# kilo-issue3-dual.net
KiCad netlist of a schematic drawn in EAGLE
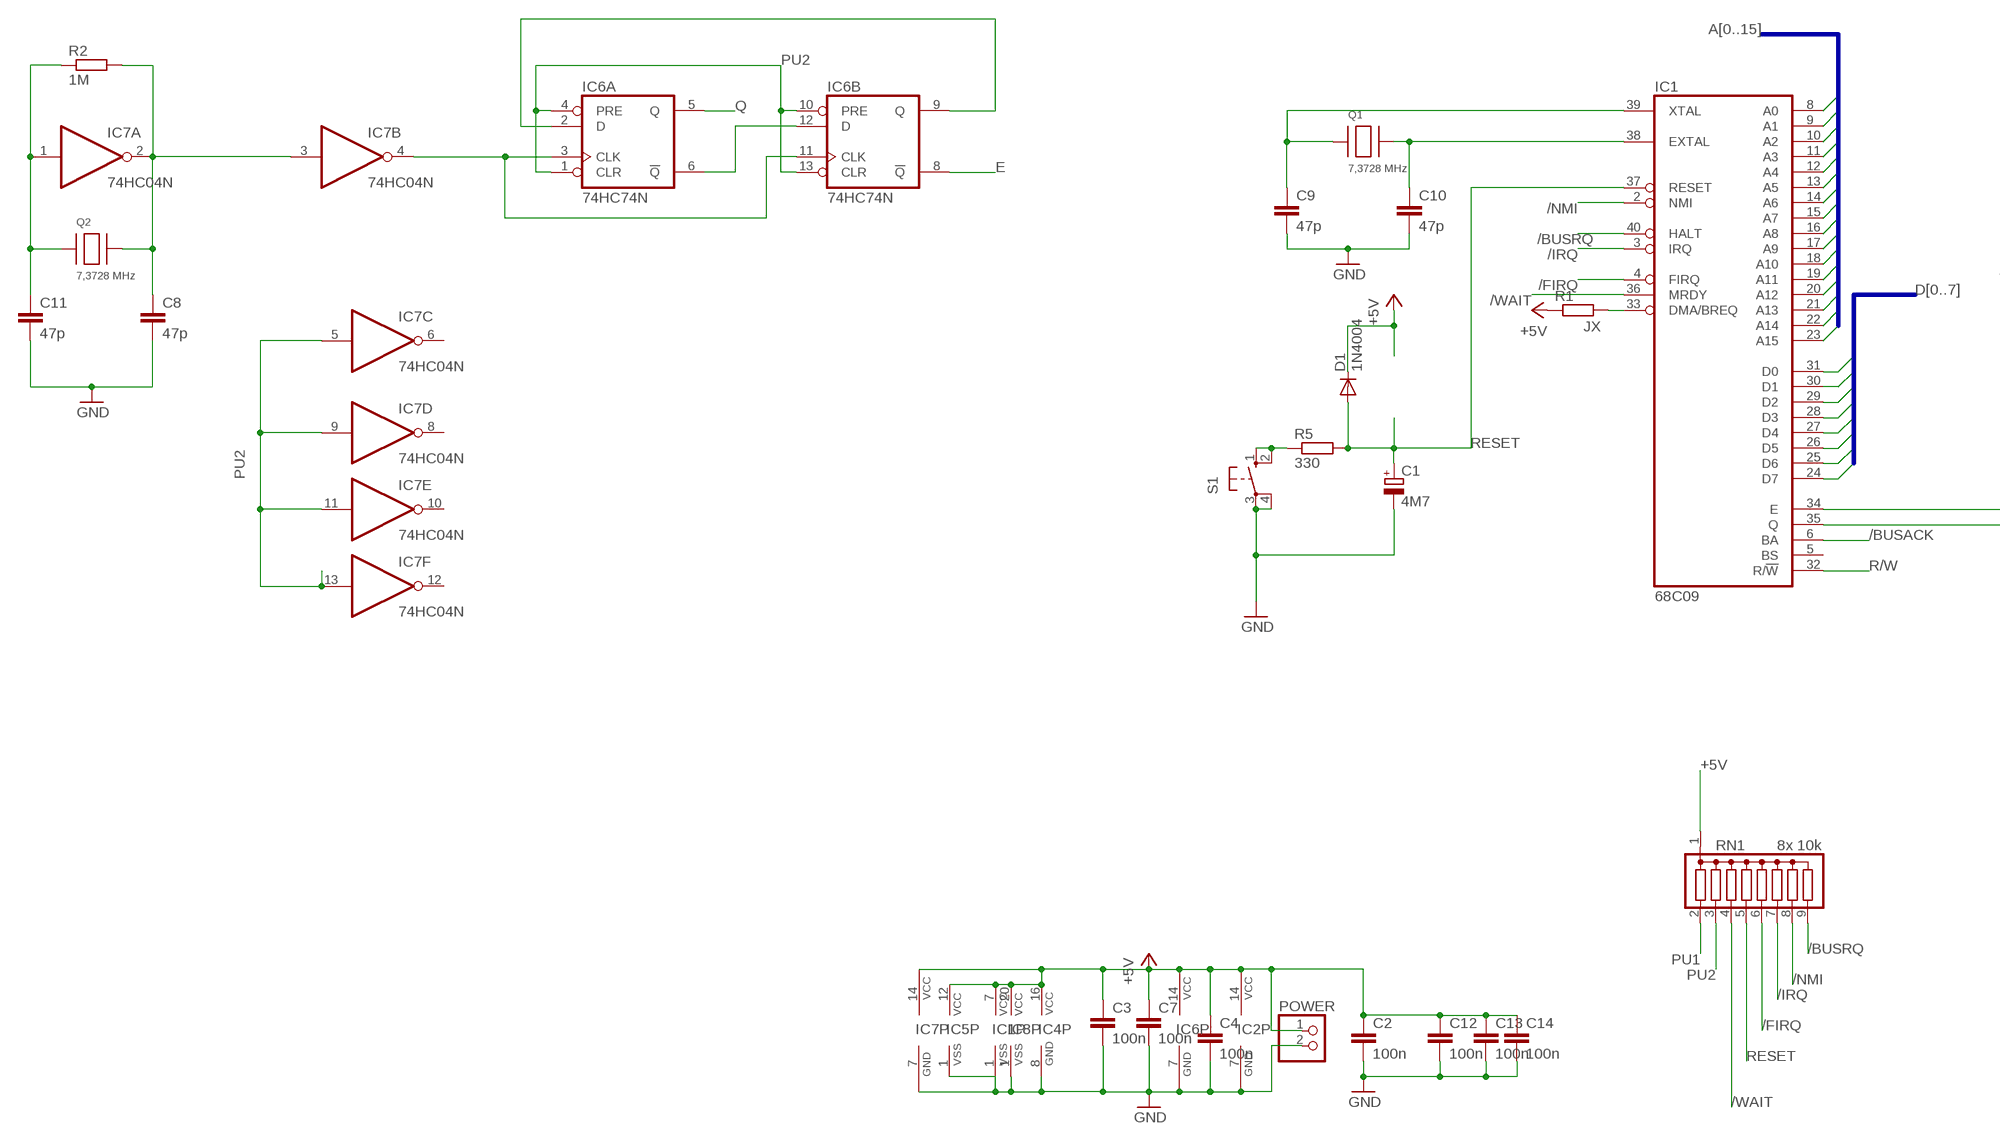
[diagram p0: schematic, sheet 1, part 1 of 2]
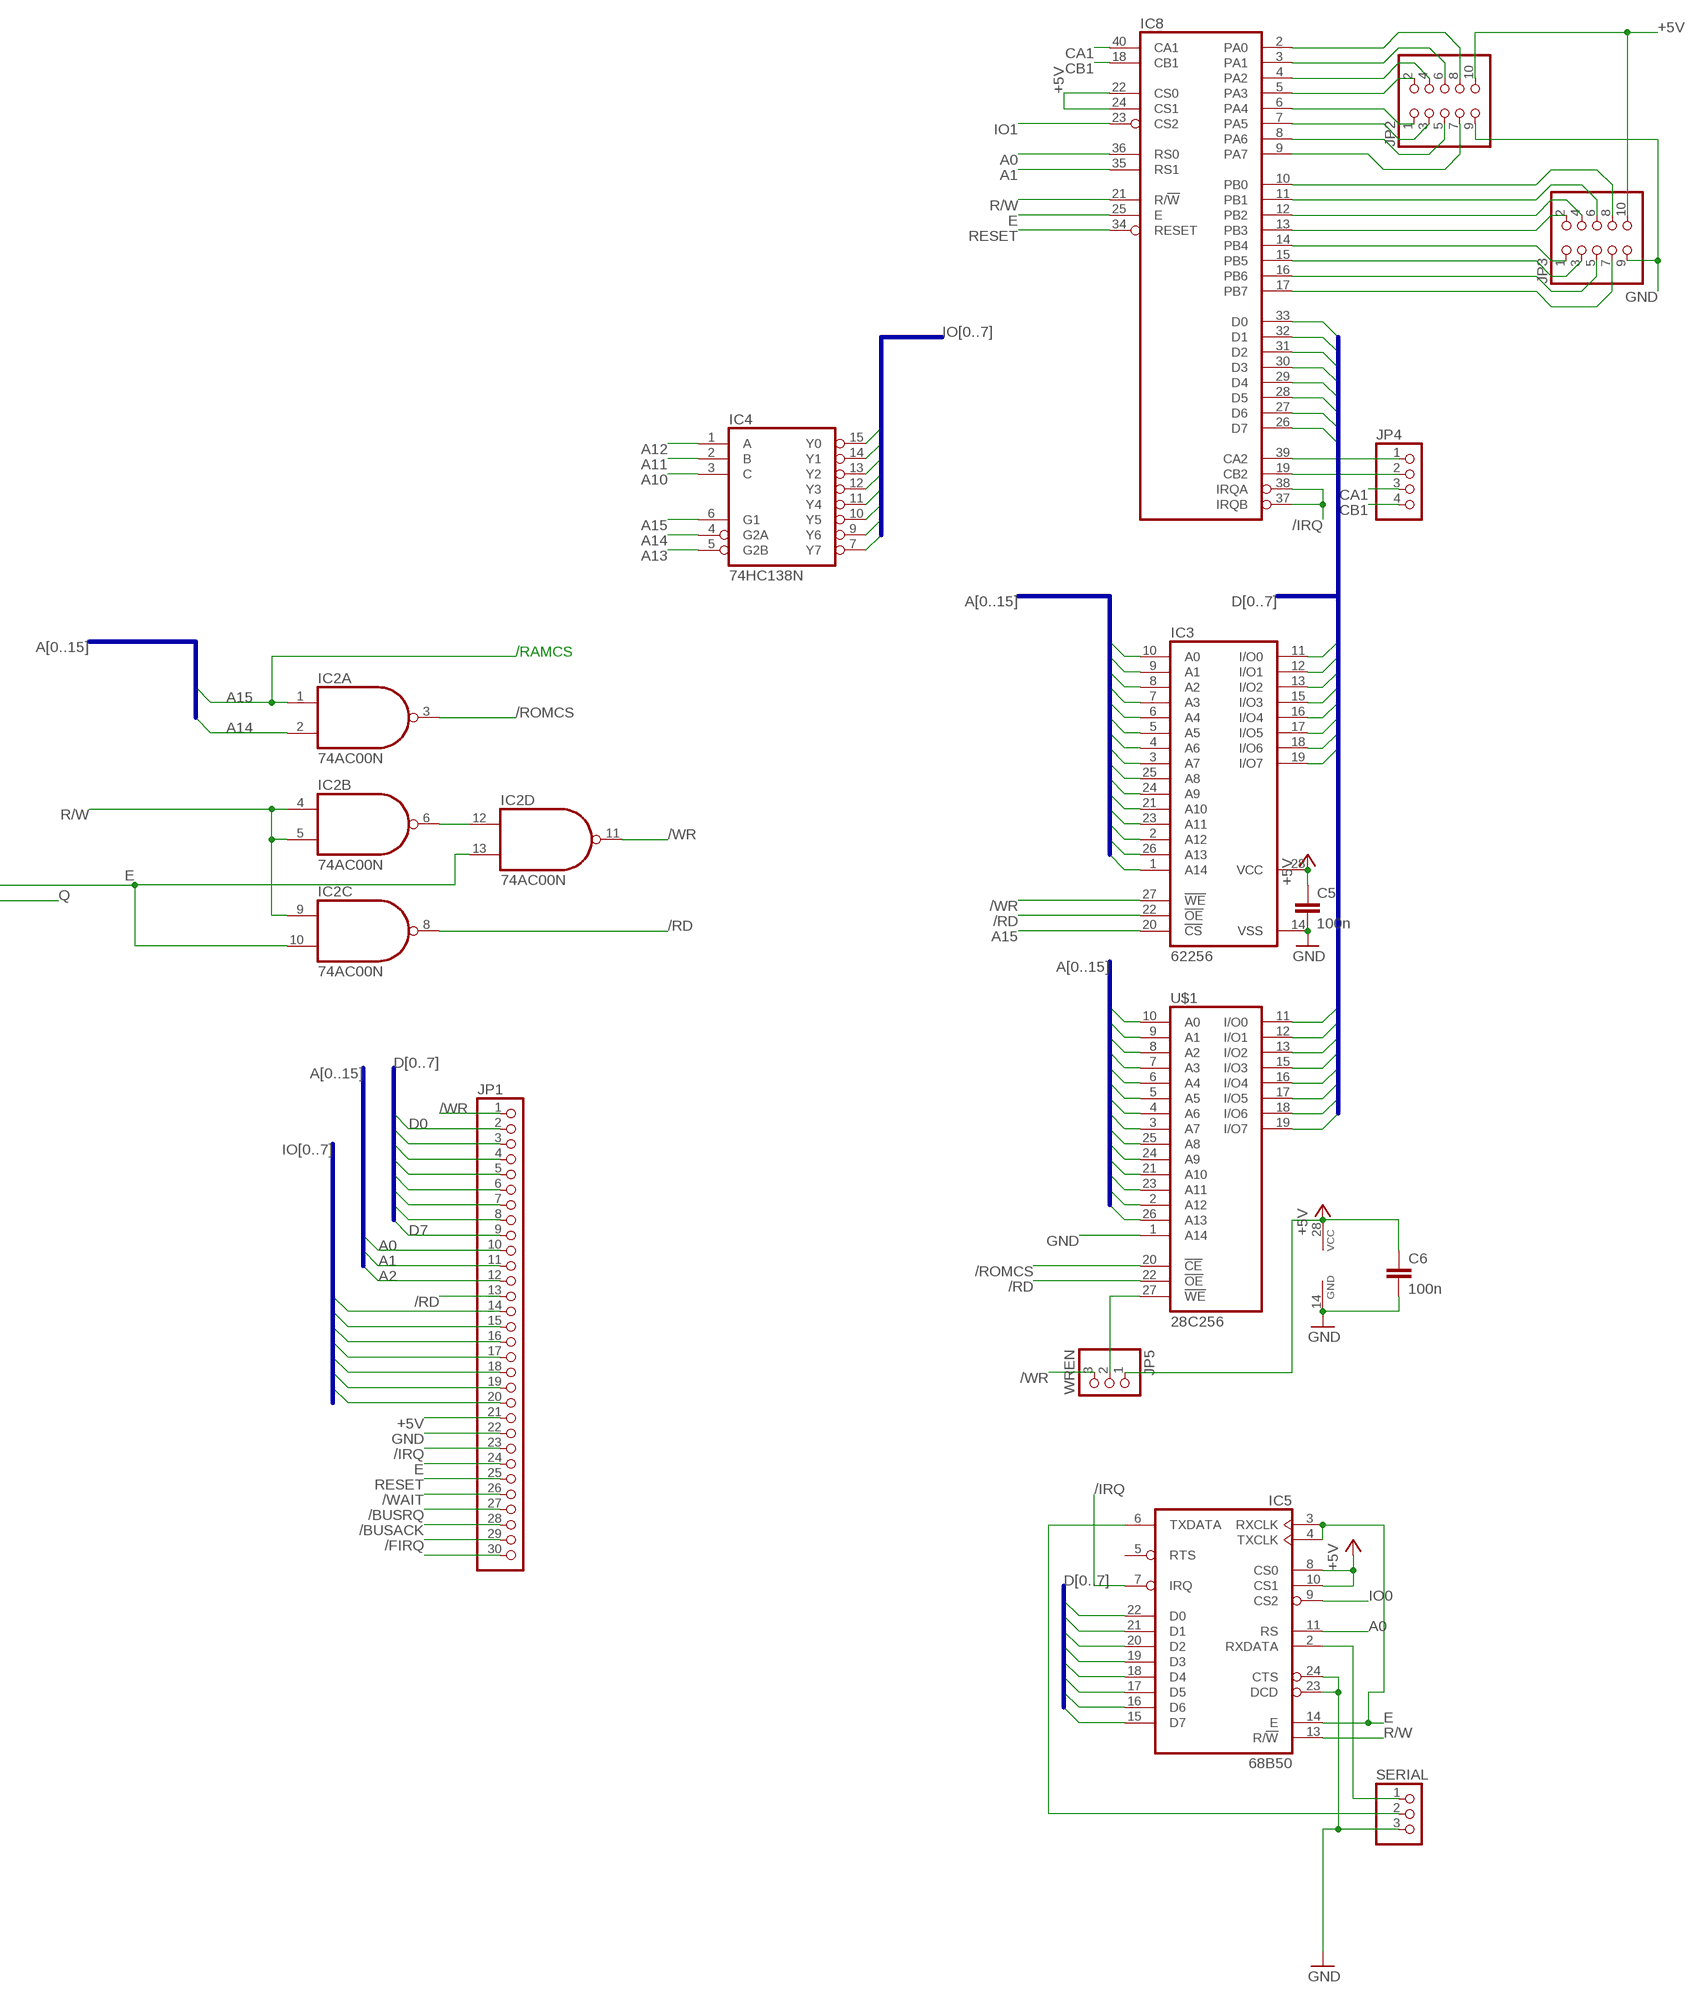
[diagram p1: schematic, sheet 1, part 2 of 2]

(export (version "E")
  (design (tool "Eeschema 10.0.6"))
  (components
    (comp (ref "C1")
      (value "4M7")
      (footprint "eagle-import:E2,5-6")
      (libsource (lib "eagle-import") (part "CPOL-EUE2.5-6"))
    )
    (comp (ref "C2")
      (value "100n")
      (footprint "eagle-import:C025-030X050")
      (libsource (lib "eagle-import") (part "C-EU025-030X050"))
    )
    (comp (ref "C3")
      (value "100n")
      (footprint "eagle-import:C025-030X050")
      (libsource (lib "eagle-import") (part "C-EU025-030X050"))
    )
    (comp (ref "C4")
      (value "100n")
      (footprint "eagle-import:C025-030X050")
      (libsource (lib "eagle-import") (part "C-EU025-030X050"))
    )
    (comp (ref "C5")
      (value "100n")
      (footprint "eagle-import:C025-030X050")
      (libsource (lib "eagle-import") (part "C-EU025-030X050"))
    )
    (comp (ref "C6")
      (value "100n")
      (footprint "eagle-import:C025-030X050")
      (libsource (lib "eagle-import") (part "C-EU025-030X050"))
    )
    (comp (ref "C7")
      (value "100n")
      (footprint "eagle-import:C025-030X050")
      (libsource (lib "eagle-import") (part "C-EU025-030X050"))
    )
    (comp (ref "C8")
      (value "47p")
      (footprint "eagle-import:C025-030X050")
      (libsource (lib "eagle-import") (part "C-EU025-030X050"))
    )
    (comp (ref "C9")
      (value "47p")
      (footprint "eagle-import:C025-030X050")
      (libsource (lib "eagle-import") (part "C-EU025-030X050"))
    )
    (comp (ref "C10")
      (value "47p")
      (footprint "eagle-import:C025-030X050")
      (libsource (lib "eagle-import") (part "C-EU025-030X050"))
    )
    (comp (ref "C11")
      (value "47p")
      (footprint "eagle-import:C025-030X050")
      (libsource (lib "eagle-import") (part "C-EU025-030X050"))
    )
    (comp (ref "C12")
      (value "100n")
      (footprint "eagle-import:C025-030X050")
      (libsource (lib "eagle-import") (part "C-EU025-030X050"))
    )
    (comp (ref "C13")
      (value "100n")
      (footprint "eagle-import:C025-030X050")
      (libsource (lib "eagle-import") (part "C-EU025-030X050"))
    )
    (comp (ref "C14")
      (value "100n")
      (footprint "eagle-import:C025-030X050")
      (libsource (lib "eagle-import") (part "C-EU025-030X050"))
    )
    (comp (ref "D1")
      (value "1N4004")
      (footprint "eagle-import:DO41-10")
      (libsource (lib "eagle-import") (part "1N4004"))
    )
    (comp (ref "IC1")
      (value "68C09")
      (footprint "eagle-import:DIL40")
      (fields (field (name "MF") "NTE ELECTRONICS") (field (name "MPN") "NTE6809"))
      (libsource (lib "eagle-import") (part "6809"))
    )
    (comp (ref "IC2")
      (value "74AC00N")
      (footprint "eagle-import:DIL14")
      (libsource (lib "eagle-import") (part "7400NALS"))
    )
    (comp (ref "IC3")
      (value "62256")
      (footprint "eagle-import:DIL28-6")
      (libsource (lib "eagle-import") (part "62256P"))
    )
    (comp (ref "IC4")
      (value "74HC138N")
      (footprint "eagle-import:DIL16")
      (libsource (lib "eagle-import") (part "74138NHC"))
    )
    (comp (ref "IC5")
      (value "68B50")
      (footprint "eagle-import:DIL24")
      (fields (field (name "MF") "NTE ELECTRONICS") (field (name "MPN") "NTE6850"))
      (libsource (lib "eagle-import") (part "6850"))
    )
    (comp (ref "IC6")
      (value "74HC74N")
      (footprint "eagle-import:DIL14")
      (libsource (lib "eagle-import") (part "7474NLS"))
    )
    (comp (ref "IC7")
      (value "74HC04N")
      (footprint "eagle-import:DIL14")
      (libsource (lib "eagle-import") (part "7404NALS"))
    )
    (comp (ref "IC8")
      (value "6821")
      (footprint "eagle-import:DIL40")
      (fields (field (name "MF") "NTE ELECTRONICS") (field (name "MPN") "NTE6821"))
      (libsource (lib "eagle-import") (part "6821"))
    )
    (comp (ref "JP1")
      (value "PINHD-1X30")
      (footprint "eagle-import:1X30")
      (libsource (lib "eagle-import") (part "PINHD-1X30"))
    )
    (comp (ref "JP2")
      (value "PINHD-2X5")
      (footprint "eagle-import:2X05")
      (libsource (lib "eagle-import") (part "PINHD-2X5"))
    )
    (comp (ref "JP3")
      (value "PINHD-2X5")
      (footprint "eagle-import:2X05")
      (libsource (lib "eagle-import") (part "PINHD-2X5"))
    )
    (comp (ref "JP4")
      (value "PINHD-1X4")
      (footprint "eagle-import:1X04")
      (libsource (lib "eagle-import") (part "PINHD-1X4"))
    )
    (comp (ref "JP5")
      (value "WREN")
      (footprint "eagle-import:1X03")
      (libsource (lib "eagle-import") (part "pinhead_325_PINHD-1X3"))
    )
    (comp (ref "POWER")
      (value "PINHD-1X2")
      (footprint "eagle-import:1X02")
      (libsource (lib "eagle-import") (part "PINHD-1X2"))
    )
    (comp (ref "Q1")
      (value "7,3728 MHz")
      (footprint "eagle-import:HC49US")
      (libsource (lib "eagle-import") (part "306010080_XTAL_8MHZ_HC49US"))
    )
    (comp (ref "Q2")
      (value "7,3728 MHz")
      (footprint "eagle-import:HC49US")
      (libsource (lib "eagle-import") (part "306010080_XTAL_8MHZ_HC49US"))
    )
    (comp (ref "R1")
      (value "JX")
      (footprint "eagle-import:M0805")
      (libsource (lib "eagle-import") (part "rcl_334_R-EU_M0805"))
    )
    (comp (ref "R2")
      (value "1M")
      (footprint "eagle-import:0207_7")
      (libsource (lib "eagle-import") (part "R-EU_0207/7"))
    )
    (comp (ref "R5")
      (value "330")
      (footprint "eagle-import:0207_7")
      (libsource (lib "eagle-import") (part "R-EU_0207/7"))
    )
    (comp (ref "RN1")
      (value "8x 10k")
      (footprint "eagle-import:SIL9")
      (libsource (lib "eagle-import") (part "G08R"))
    )
    (comp (ref "S1")
      (value "40-XX")
      (footprint "eagle-import:B3F-40XX")
      (fields (field (name "MF") "OMRON COMPONENTS USA") (field (name "MPN") "B3F-4000"))
      (libsource (lib "eagle-import") (part "40-XX"))
    )
    (comp (ref "SERIAL")
      (value "PINHD-1X3")
      (footprint "eagle-import:1X03")
      (libsource (lib "eagle-import") (part "PINHD-1X3"))
    )
    (comp (ref "U$1")
      (value "28C256")
      (footprint "eagle-import:DIL28")
      (libsource (lib "eagle-import") (part "28C256"))
    )
  )
  (nets
    (net (code "1") (name "+5V") (class "Default")
      (node (ref "C12") (pin "1") (pinfunction "1_1") (pintype "passive"))
      (node (ref "C13") (pin "1") (pinfunction "1_1") (pintype "passive"))
      (node (ref "C14") (pin "1") (pinfunction "1_1") (pintype "passive"))
      (node (ref "C2") (pin "1") (pinfunction "1_1") (pintype "passive"))
      (node (ref "C3") (pin "1") (pinfunction "1_1") (pintype "passive"))
      (node (ref "C4") (pin "1") (pinfunction "1_1") (pintype "passive"))
      (node (ref "C5") (pin "1") (pinfunction "1_1") (pintype "passive"))
      (node (ref "C6") (pin "1") (pinfunction "1_1") (pintype "passive"))
      (node (ref "C7") (pin "1") (pinfunction "1_1") (pintype "passive"))
      (node (ref "D1") (pin "C") (pinfunction "C_C") (pintype "passive"))
      (node (ref "IC1") (pin "7") (pinfunction "VCC_7") (pintype "power_in"))
      (node (ref "IC2") (pin "14") (pinfunction "VCC_14") (pintype "power_in"))
      (node (ref "IC3") (pin "28") (pinfunction "VCC_28") (pintype "power_in"))
      (node (ref "IC4") (pin "16") (pinfunction "VCC_16") (pintype "power_in"))
      (node (ref "IC5") (pin "10") (pinfunction "CS1_10") (pintype "input"))
      (node (ref "IC5") (pin "12") (pinfunction "VCC_12") (pintype "power_in"))
      (node (ref "IC5") (pin "8") (pinfunction "CS0_8") (pintype "input"))
      (node (ref "IC6") (pin "14") (pinfunction "VCC_14") (pintype "power_in"))
      (node (ref "IC7") (pin "14") (pinfunction "VCC_14") (pintype "power_in"))
      (node (ref "IC8") (pin "20") (pinfunction "VCC_20") (pintype "power_in"))
      (node (ref "IC8") (pin "22") (pinfunction "CS0_22") (pintype "input"))
      (node (ref "IC8") (pin "24") (pinfunction "CS1_24") (pintype "input"))
      (node (ref "JP1") (pin "21") (pinfunction "21_21") (pintype "passive"))
      (node (ref "JP2") (pin "10") (pinfunction "10_10") (pintype "passive"))
      (node (ref "JP3") (pin "10") (pinfunction "10_10") (pintype "passive"))
      (node (ref "JP5") (pin "1") (pinfunction "1_1") (pintype "passive"))
      (node (ref "POWER") (pin "1") (pinfunction "1_1") (pintype "passive"))
      (node (ref "R1") (pin "1") (pinfunction "1_1") (pintype "passive"))
      (node (ref "RN1") (pin "1") (pinfunction "1_1") (pintype "passive"))
      (node (ref "U$1") (pin "28") (pinfunction "VCC_28") (pintype "power_in"))
    )
    (net (code "5") (name "A0") (class "Default")
      (node (ref "IC1") (pin "8") (pinfunction "A0_8") (pintype "tri_state"))
      (node (ref "IC3") (pin "10") (pinfunction "A0_10") (pintype "input"))
      (node (ref "IC5") (pin "11") (pinfunction "RS_11") (pintype "input"))
      (node (ref "IC8") (pin "36") (pinfunction "RS0_36") (pintype "input"))
      (node (ref "JP1") (pin "10") (pinfunction "10_10") (pintype "passive"))
      (node (ref "U$1") (pin "10") (pinfunction "A0_10") (pintype "input"))
    )
    (net (code "6") (name "A1") (class "Default")
      (node (ref "IC1") (pin "9") (pinfunction "A1_9") (pintype "tri_state"))
      (node (ref "IC3") (pin "9") (pinfunction "A1_9") (pintype "input"))
      (node (ref "IC8") (pin "35") (pinfunction "RS1_35") (pintype "input"))
      (node (ref "JP1") (pin "11") (pinfunction "11_11") (pintype "passive"))
      (node (ref "U$1") (pin "9") (pinfunction "A1_9") (pintype "input"))
    )
    (net (code "7") (name "A2") (class "Default")
      (node (ref "IC1") (pin "10") (pinfunction "A2_10") (pintype "tri_state"))
      (node (ref "IC3") (pin "8") (pinfunction "A2_8") (pintype "input"))
      (node (ref "JP1") (pin "12") (pinfunction "12_12") (pintype "passive"))
      (node (ref "U$1") (pin "8") (pinfunction "A2_8") (pintype "input"))
    )
    (net (code "8") (name "A3") (class "Default")
      (node (ref "IC1") (pin "11") (pinfunction "A3_11") (pintype "tri_state"))
      (node (ref "IC3") (pin "7") (pinfunction "A3_7") (pintype "input"))
      (node (ref "U$1") (pin "7") (pinfunction "A3_7") (pintype "input"))
    )
    (net (code "9") (name "A4") (class "Default")
      (node (ref "IC1") (pin "12") (pinfunction "A4_12") (pintype "tri_state"))
      (node (ref "IC3") (pin "6") (pinfunction "A4_6") (pintype "input"))
      (node (ref "U$1") (pin "6") (pinfunction "A4_6") (pintype "input"))
    )
    (net (code "10") (name "A5") (class "Default")
      (node (ref "IC1") (pin "13") (pinfunction "A5_13") (pintype "tri_state"))
      (node (ref "IC3") (pin "5") (pinfunction "A5_5") (pintype "input"))
      (node (ref "U$1") (pin "5") (pinfunction "A5_5") (pintype "input"))
    )
    (net (code "11") (name "A6") (class "Default")
      (node (ref "IC1") (pin "14") (pinfunction "A6_14") (pintype "tri_state"))
      (node (ref "IC3") (pin "4") (pinfunction "A6_4") (pintype "input"))
      (node (ref "U$1") (pin "4") (pinfunction "A6_4") (pintype "input"))
    )
    (net (code "12") (name "A7") (class "Default")
      (node (ref "IC1") (pin "15") (pinfunction "A7_15") (pintype "tri_state"))
      (node (ref "IC3") (pin "3") (pinfunction "A7_3") (pintype "input"))
      (node (ref "U$1") (pin "3") (pinfunction "A7_3") (pintype "input"))
    )
    (net (code "13") (name "A8") (class "Default")
      (node (ref "IC1") (pin "16") (pinfunction "A8_16") (pintype "tri_state"))
      (node (ref "IC3") (pin "25") (pinfunction "A8_25") (pintype "input"))
      (node (ref "U$1") (pin "25") (pinfunction "A8_25") (pintype "input"))
    )
    (net (code "14") (name "A9") (class "Default")
      (node (ref "IC1") (pin "17") (pinfunction "A9_17") (pintype "tri_state"))
      (node (ref "IC3") (pin "24") (pinfunction "A9_24") (pintype "input"))
      (node (ref "U$1") (pin "24") (pinfunction "A9_24") (pintype "input"))
    )
    (net (code "15") (name "A10") (class "Default")
      (node (ref "IC1") (pin "18") (pinfunction "A10_18") (pintype "tri_state"))
      (node (ref "IC3") (pin "21") (pinfunction "A10_21") (pintype "input"))
      (node (ref "IC4") (pin "3") (pinfunction "C_3") (pintype "input"))
      (node (ref "U$1") (pin "21") (pinfunction "A10_21") (pintype "input"))
    )
    (net (code "16") (name "A11") (class "Default")
      (node (ref "IC1") (pin "19") (pinfunction "A11_19") (pintype "tri_state"))
      (node (ref "IC3") (pin "23") (pinfunction "A11_23") (pintype "input"))
      (node (ref "IC4") (pin "2") (pinfunction "B_2") (pintype "input"))
      (node (ref "U$1") (pin "23") (pinfunction "A11_23") (pintype "input"))
    )
    (net (code "17") (name "A12") (class "Default")
      (node (ref "IC1") (pin "20") (pinfunction "A12_20") (pintype "tri_state"))
      (node (ref "IC3") (pin "2") (pinfunction "A12_2") (pintype "input"))
      (node (ref "IC4") (pin "1") (pinfunction "A_1") (pintype "input"))
      (node (ref "U$1") (pin "2") (pinfunction "A12_2") (pintype "input"))
    )
    (net (code "18") (name "A13") (class "Default")
      (node (ref "IC1") (pin "21") (pinfunction "A13_21") (pintype "tri_state"))
      (node (ref "IC3") (pin "26") (pinfunction "A13_26") (pintype "input"))
      (node (ref "IC4") (pin "5") (pinfunction "G2B_5") (pintype "input"))
      (node (ref "U$1") (pin "26") (pinfunction "A13_26") (pintype "input"))
    )
    (net (code "19") (name "A14") (class "Default")
      (node (ref "IC1") (pin "22") (pinfunction "A14_22") (pintype "tri_state"))
      (node (ref "IC2") (pin "2") (pinfunction "I1_2") (pintype "input"))
      (node (ref "IC3") (pin "1") (pinfunction "A14_1") (pintype "input"))
      (node (ref "IC4") (pin "4") (pinfunction "G2A_4") (pintype "input"))
    )
    (net (code "20") (name "A15") (class "Default")
      (node (ref "IC1") (pin "23") (pinfunction "A15_23") (pintype "tri_state"))
      (node (ref "IC2") (pin "1") (pinfunction "I0_1") (pintype "input"))
      (node (ref "IC3") (pin "20") (pinfunction "~{CS}_20") (pintype "input"))
      (node (ref "IC4") (pin "6") (pinfunction "G1_6") (pintype "input"))
    )
    (net (code "21") (name "CA1") (class "Default")
      (node (ref "IC8") (pin "40") (pinfunction "CA1_40") (pintype "input"))
      (node (ref "JP4") (pin "3") (pinfunction "3_3") (pintype "passive"))
    )
    (net (code "22") (name "CB1") (class "Default")
      (node (ref "IC8") (pin "18") (pinfunction "CB1_18") (pintype "input"))
      (node (ref "JP4") (pin "4") (pinfunction "4_4") (pintype "passive"))
    )
    (net (code "23") (name "D0") (class "Default")
      (node (ref "IC1") (pin "31") (pinfunction "D0_31") (pintype "bidirectional"))
      (node (ref "IC3") (pin "11") (pinfunction "I/O0_11") (pintype "bidirectional"))
      (node (ref "IC5") (pin "22") (pinfunction "D0_22") (pintype "bidirectional"))
      (node (ref "IC8") (pin "33") (pinfunction "D0_33") (pintype "bidirectional"))
      (node (ref "JP1") (pin "2") (pinfunction "2_2") (pintype "passive"))
      (node (ref "U$1") (pin "11") (pinfunction "I/O0_11") (pintype "tri_state"))
    )
    (net (code "24") (name "D1") (class "Default")
      (node (ref "IC1") (pin "30") (pinfunction "D1_30") (pintype "bidirectional"))
      (node (ref "IC3") (pin "12") (pinfunction "I/O1_12") (pintype "bidirectional"))
      (node (ref "IC5") (pin "21") (pinfunction "D1_21") (pintype "bidirectional"))
      (node (ref "IC8") (pin "32") (pinfunction "D1_32") (pintype "bidirectional"))
      (node (ref "JP1") (pin "3") (pinfunction "3_3") (pintype "passive"))
      (node (ref "U$1") (pin "12") (pinfunction "I/O1_12") (pintype "tri_state"))
    )
    (net (code "25") (name "D2") (class "Default")
      (node (ref "IC1") (pin "29") (pinfunction "D2_29") (pintype "bidirectional"))
      (node (ref "IC3") (pin "13") (pinfunction "I/O2_13") (pintype "bidirectional"))
      (node (ref "IC5") (pin "20") (pinfunction "D2_20") (pintype "bidirectional"))
      (node (ref "IC8") (pin "31") (pinfunction "D2_31") (pintype "bidirectional"))
      (node (ref "JP1") (pin "4") (pinfunction "4_4") (pintype "passive"))
      (node (ref "U$1") (pin "13") (pinfunction "I/O2_13") (pintype "tri_state"))
    )
    (net (code "26") (name "D3") (class "Default")
      (node (ref "IC1") (pin "28") (pinfunction "D3_28") (pintype "bidirectional"))
      (node (ref "IC3") (pin "15") (pinfunction "I/O3_15") (pintype "bidirectional"))
      (node (ref "IC5") (pin "19") (pinfunction "D3_19") (pintype "bidirectional"))
      (node (ref "IC8") (pin "30") (pinfunction "D3_30") (pintype "bidirectional"))
      (node (ref "JP1") (pin "5") (pinfunction "5_5") (pintype "passive"))
      (node (ref "U$1") (pin "15") (pinfunction "I/O3_15") (pintype "tri_state"))
    )
    (net (code "27") (name "D4") (class "Default")
      (node (ref "IC1") (pin "27") (pinfunction "D4_27") (pintype "bidirectional"))
      (node (ref "IC3") (pin "16") (pinfunction "I/O4_16") (pintype "bidirectional"))
      (node (ref "IC5") (pin "18") (pinfunction "D4_18") (pintype "bidirectional"))
      (node (ref "IC8") (pin "29") (pinfunction "D4_29") (pintype "bidirectional"))
      (node (ref "JP1") (pin "6") (pinfunction "6_6") (pintype "passive"))
      (node (ref "U$1") (pin "16") (pinfunction "I/O4_16") (pintype "tri_state"))
    )
    (net (code "28") (name "D5") (class "Default")
      (node (ref "IC1") (pin "26") (pinfunction "D5_26") (pintype "bidirectional"))
      (node (ref "IC3") (pin "17") (pinfunction "I/O5_17") (pintype "bidirectional"))
      (node (ref "IC5") (pin "17") (pinfunction "D5_17") (pintype "bidirectional"))
      (node (ref "IC8") (pin "28") (pinfunction "D5_28") (pintype "bidirectional"))
      (node (ref "JP1") (pin "7") (pinfunction "7_7") (pintype "passive"))
      (node (ref "U$1") (pin "17") (pinfunction "I/O5_17") (pintype "tri_state"))
    )
    (net (code "29") (name "D6") (class "Default")
      (node (ref "IC1") (pin "25") (pinfunction "D6_25") (pintype "bidirectional"))
      (node (ref "IC3") (pin "18") (pinfunction "I/O6_18") (pintype "bidirectional"))
      (node (ref "IC5") (pin "16") (pinfunction "D6_16") (pintype "bidirectional"))
      (node (ref "IC8") (pin "27") (pinfunction "D6_27") (pintype "bidirectional"))
      (node (ref "JP1") (pin "8") (pinfunction "8_8") (pintype "passive"))
      (node (ref "U$1") (pin "18") (pinfunction "I/O6_18") (pintype "tri_state"))
    )
    (net (code "30") (name "D7") (class "Default")
      (node (ref "IC1") (pin "24") (pinfunction "D7_24") (pintype "bidirectional"))
      (node (ref "IC3") (pin "19") (pinfunction "I/O7_19") (pintype "bidirectional"))
      (node (ref "IC5") (pin "15") (pinfunction "D7_15") (pintype "bidirectional"))
      (node (ref "IC8") (pin "26") (pinfunction "D7_26") (pintype "bidirectional"))
      (node (ref "JP1") (pin "9") (pinfunction "9_9") (pintype "passive"))
      (node (ref "U$1") (pin "19") (pinfunction "I/O7_19") (pintype "tri_state"))
    )
    (net (code "31") (name "E") (class "Default")
      (node (ref "IC1") (pin "34") (pinfunction "E_34") (pintype "output"))
      (node (ref "IC2") (pin "10") (pinfunction "I1_10") (pintype "input"))
      (node (ref "IC2") (pin "13") (pinfunction "I1_13") (pintype "input"))
      (node (ref "IC5") (pin "14") (pinfunction "E_14") (pintype "input"))
      (node (ref "IC5") (pin "3") (pinfunction "RXCLK_3") (pintype "input"))
      (node (ref "IC5") (pin "4") (pinfunction "TXCLK_4") (pintype "input"))
      (node (ref "IC6") (pin "8") (pinfunction "~{Q}_8") (pintype "output"))
      (node (ref "IC8") (pin "25") (pinfunction "E_25") (pintype "input"))
      (node (ref "JP1") (pin "24") (pinfunction "24_24") (pintype "passive"))
    )
    (net (code "32") (name "GND") (class "Default")
      (node (ref "C1") (pin "-") (pinfunction "-_-") (pintype "passive"))
      (node (ref "C10") (pin "2") (pinfunction "2_2") (pintype "passive"))
      (node (ref "C11") (pin "2") (pinfunction "2_2") (pintype "passive"))
      (node (ref "C12") (pin "2") (pinfunction "2_2") (pintype "passive"))
      (node (ref "C13") (pin "2") (pinfunction "2_2") (pintype "passive"))
      (node (ref "C14") (pin "2") (pinfunction "2_2") (pintype "passive"))
      (node (ref "C2") (pin "2") (pinfunction "2_2") (pintype "passive"))
      (node (ref "C3") (pin "2") (pinfunction "2_2") (pintype "passive"))
      (node (ref "C4") (pin "2") (pinfunction "2_2") (pintype "passive"))
      (node (ref "C5") (pin "2") (pinfunction "2_2") (pintype "passive"))
      (node (ref "C6") (pin "2") (pinfunction "2_2") (pintype "passive"))
      (node (ref "C7") (pin "2") (pinfunction "2_2") (pintype "passive"))
      (node (ref "C8") (pin "2") (pinfunction "2_2") (pintype "passive"))
      (node (ref "C9") (pin "2") (pinfunction "2_2") (pintype "passive"))
      (node (ref "IC1") (pin "1") (pinfunction "VSS_1") (pintype "power_in"))
      (node (ref "IC2") (pin "7") (pinfunction "GND_7") (pintype "power_in"))
      (node (ref "IC3") (pin "14") (pinfunction "VSS_14") (pintype "power_in"))
      (node (ref "IC4") (pin "8") (pinfunction "GND_8") (pintype "power_in"))
      (node (ref "IC5") (pin "1") (pinfunction "VSS_1") (pintype "power_in"))
      (node (ref "IC5") (pin "23") (pinfunction "DCD_23") (pintype "input"))
      (node (ref "IC5") (pin "24") (pinfunction "CTS_24") (pintype "input"))
      (node (ref "IC6") (pin "7") (pinfunction "GND_7") (pintype "power_in"))
      (node (ref "IC7") (pin "7") (pinfunction "GND_7") (pintype "power_in"))
      (node (ref "IC8") (pin "1") (pinfunction "VSS_1") (pintype "power_in"))
      (node (ref "JP1") (pin "22") (pinfunction "22_22") (pintype "passive"))
      (node (ref "JP2") (pin "9") (pinfunction "9_9") (pintype "passive"))
      (node (ref "JP3") (pin "9") (pinfunction "9_9") (pintype "passive"))
      (node (ref "POWER") (pin "2") (pinfunction "2_2") (pintype "passive"))
      (node (ref "S1") (pin "3") (pinfunction "P_3") (pintype "passive"))
      (node (ref "S1") (pin "4") (pinfunction "P1_4") (pintype "passive"))
      (node (ref "SERIAL") (pin "3") (pinfunction "3_3") (pintype "passive"))
      (node (ref "U$1") (pin "1") (pinfunction "A14_1") (pintype "input"))
      (node (ref "U$1") (pin "14") (pinfunction "GND_14") (pintype "power_in"))
    )
    (net (code "33") (name "IO0") (class "Default")
      (node (ref "IC4") (pin "15") (pinfunction "Y0_15") (pintype "output"))
      (node (ref "IC5") (pin "9") (pinfunction "CS2_9") (pintype "input"))
    )
    (net (code "34") (name "IO1") (class "Default")
      (node (ref "IC4") (pin "14") (pinfunction "Y1_14") (pintype "output"))
      (node (ref "IC8") (pin "23") (pinfunction "CS2_23") (pintype "input"))
      (node (ref "JP1") (pin "14") (pinfunction "14_14") (pintype "passive"))
    )
    (net (code "35") (name "IO2") (class "Default")
      (node (ref "IC4") (pin "13") (pinfunction "Y2_13") (pintype "output"))
      (node (ref "JP1") (pin "15") (pinfunction "15_15") (pintype "passive"))
    )
    (net (code "36") (name "IO3") (class "Default")
      (node (ref "IC4") (pin "12") (pinfunction "Y3_12") (pintype "output"))
      (node (ref "JP1") (pin "16") (pinfunction "16_16") (pintype "passive"))
    )
    (net (code "37") (name "IO4") (class "Default")
      (node (ref "IC4") (pin "11") (pinfunction "Y4_11") (pintype "output"))
      (node (ref "JP1") (pin "17") (pinfunction "17_17") (pintype "passive"))
    )
    (net (code "38") (name "IO5") (class "Default")
      (node (ref "IC4") (pin "10") (pinfunction "Y5_10") (pintype "output"))
      (node (ref "JP1") (pin "18") (pinfunction "18_18") (pintype "passive"))
    )
    (net (code "39") (name "IO6") (class "Default")
      (node (ref "IC4") (pin "9") (pinfunction "Y6_9") (pintype "output"))
      (node (ref "JP1") (pin "19") (pinfunction "19_19") (pintype "passive"))
    )
    (net (code "40") (name "IO7") (class "Default")
      (node (ref "IC4") (pin "7") (pinfunction "Y7_7") (pintype "output"))
      (node (ref "JP1") (pin "20") (pinfunction "20_20") (pintype "passive"))
    )
    (net (code "41") (name "Net-(IC1A-DMA{slash}BREQ)") (class "Default")
      (node (ref "IC1") (pin "33") (pinfunction "DMA/BREQ_33") (pintype "input"))
      (node (ref "R1") (pin "2") (pinfunction "2_2") (pintype "passive"))
    )
    (net (code "42") (name "Net-(IC1A-EXTAL)") (class "Default")
      (node (ref "C10") (pin "1") (pinfunction "1_1") (pintype "passive"))
      (node (ref "IC1") (pin "38") (pinfunction "EXTAL_38") (pintype "input"))
      (node (ref "Q1") (pin "P$2") (pinfunction "P$2_P$2") (pintype "passive"))
    )
    (net (code "43") (name "Net-(IC1A-XTAL)") (class "Default")
      (node (ref "C9") (pin "1") (pinfunction "1_1") (pintype "passive"))
      (node (ref "IC1") (pin "39") (pinfunction "XTAL_39") (pintype "input"))
      (node (ref "Q1") (pin "P$1") (pinfunction "P$1_P$1") (pintype "passive"))
    )
    (net (code "44") (name "Net-(IC2B-O)") (class "Default")
      (node (ref "IC2") (pin "12") (pinfunction "I0_12") (pintype "input"))
      (node (ref "IC2") (pin "6") (pinfunction "O_6") (pintype "output"))
    )
    (net (code "45") (name "Net-(IC5A-RXDATA)") (class "Default")
      (node (ref "IC5") (pin "2") (pinfunction "RXDATA_2") (pintype "input"))
      (node (ref "SERIAL") (pin "1") (pinfunction "1_1") (pintype "passive"))
    )
    (net (code "46") (name "Net-(IC5A-TXDATA)") (class "Default")
      (node (ref "IC5") (pin "6") (pinfunction "TXDATA_6") (pintype "output"))
      (node (ref "SERIAL") (pin "2") (pinfunction "2_2") (pintype "passive"))
    )
    (net (code "47") (name "Net-(IC6A-CLK)") (class "Default")
      (node (ref "IC6") (pin "11") (pinfunction "CLK_11") (pintype "input"))
      (node (ref "IC6") (pin "3") (pinfunction "CLK_3") (pintype "input"))
      (node (ref "IC7") (pin "4") (pinfunction "O_4") (pintype "output"))
    )
    (net (code "48") (name "Net-(IC6A-D)") (class "Default")
      (node (ref "IC6") (pin "2") (pinfunction "D_2") (pintype "input"))
      (node (ref "IC6") (pin "9") (pinfunction "Q_9") (pintype "output"))
    )
    (net (code "49") (name "Net-(IC6A-~{Q})") (class "Default")
      (node (ref "IC6") (pin "12") (pinfunction "D_12") (pintype "input"))
      (node (ref "IC6") (pin "6") (pinfunction "~{Q}_6") (pintype "output"))
    )
    (net (code "50") (name "Net-(IC7A-I)") (class "Default")
      (node (ref "C11") (pin "1") (pinfunction "1_1") (pintype "passive"))
      (node (ref "IC7") (pin "1") (pinfunction "I_1") (pintype "input"))
      (node (ref "Q2") (pin "P$1") (pinfunction "P$1_P$1") (pintype "passive"))
      (node (ref "R2") (pin "1") (pinfunction "1_1") (pintype "passive"))
    )
    (net (code "51") (name "Net-(IC7A-O)") (class "Default")
      (node (ref "C8") (pin "1") (pinfunction "1_1") (pintype "passive"))
      (node (ref "IC7") (pin "2") (pinfunction "O_2") (pintype "output"))
      (node (ref "IC7") (pin "3") (pinfunction "I_3") (pintype "input"))
      (node (ref "Q2") (pin "P$2") (pinfunction "P$2_P$2") (pintype "passive"))
      (node (ref "R2") (pin "2") (pinfunction "2_2") (pintype "passive"))
    )
    (net (code "52") (name "Net-(IC8A-CA2)") (class "Default")
      (node (ref "IC8") (pin "39") (pinfunction "CA2_39") (pintype "bidirectional"))
      (node (ref "JP4") (pin "1") (pinfunction "1_1") (pintype "passive"))
    )
    (net (code "53") (name "Net-(IC8A-CB2)") (class "Default")
      (node (ref "IC8") (pin "19") (pinfunction "CB2_19") (pintype "bidirectional"))
      (node (ref "JP4") (pin "2") (pinfunction "2_2") (pintype "passive"))
    )
    (net (code "54") (name "Net-(IC8A-PA0)") (class "Default")
      (node (ref "IC8") (pin "2") (pinfunction "PA0_2") (pintype "bidirectional"))
      (node (ref "JP2") (pin "8") (pinfunction "8_8") (pintype "passive"))
    )
    (net (code "55") (name "Net-(IC8A-PA1)") (class "Default")
      (node (ref "IC8") (pin "3") (pinfunction "PA1_3") (pintype "bidirectional"))
      (node (ref "JP2") (pin "6") (pinfunction "6_6") (pintype "passive"))
    )
    (net (code "56") (name "Net-(IC8A-PA2)") (class "Default")
      (node (ref "IC8") (pin "4") (pinfunction "PA2_4") (pintype "bidirectional"))
      (node (ref "JP2") (pin "4") (pinfunction "4_4") (pintype "passive"))
    )
    (net (code "57") (name "Net-(IC8A-PA3)") (class "Default")
      (node (ref "IC8") (pin "5") (pinfunction "PA3_5") (pintype "bidirectional"))
      (node (ref "JP2") (pin "2") (pinfunction "2_2") (pintype "passive"))
    )
    (net (code "58") (name "Net-(IC8A-PA4)") (class "Default")
      (node (ref "IC8") (pin "6") (pinfunction "PA4_6") (pintype "bidirectional"))
      (node (ref "JP2") (pin "1") (pinfunction "1_1") (pintype "passive"))
    )
    (net (code "59") (name "Net-(IC8A-PA5)") (class "Default")
      (node (ref "IC8") (pin "7") (pinfunction "PA5_7") (pintype "bidirectional"))
      (node (ref "JP2") (pin "3") (pinfunction "3_3") (pintype "passive"))
    )
    (net (code "60") (name "Net-(IC8A-PA6)") (class "Default")
      (node (ref "IC8") (pin "8") (pinfunction "PA6_8") (pintype "bidirectional"))
      (node (ref "JP2") (pin "5") (pinfunction "5_5") (pintype "passive"))
    )
    (net (code "61") (name "Net-(IC8A-PA7)") (class "Default")
      (node (ref "IC8") (pin "9") (pinfunction "PA7_9") (pintype "bidirectional"))
      (node (ref "JP2") (pin "7") (pinfunction "7_7") (pintype "passive"))
    )
    (net (code "62") (name "Net-(IC8A-PB0)") (class "Default")
      (node (ref "IC8") (pin "10") (pinfunction "PB0_10") (pintype "bidirectional"))
      (node (ref "JP3") (pin "8") (pinfunction "8_8") (pintype "passive"))
    )
    (net (code "63") (name "Net-(IC8A-PB1)") (class "Default")
      (node (ref "IC8") (pin "11") (pinfunction "PB1_11") (pintype "bidirectional"))
      (node (ref "JP3") (pin "6") (pinfunction "6_6") (pintype "passive"))
    )
    (net (code "64") (name "Net-(IC8A-PB2)") (class "Default")
      (node (ref "IC8") (pin "12") (pinfunction "PB2_12") (pintype "bidirectional"))
      (node (ref "JP3") (pin "4") (pinfunction "4_4") (pintype "passive"))
    )
    (net (code "65") (name "Net-(IC8A-PB3)") (class "Default")
      (node (ref "IC8") (pin "13") (pinfunction "PB3_13") (pintype "bidirectional"))
      (node (ref "JP3") (pin "2") (pinfunction "2_2") (pintype "passive"))
    )
    (net (code "66") (name "Net-(IC8A-PB4)") (class "Default")
      (node (ref "IC8") (pin "14") (pinfunction "PB4_14") (pintype "bidirectional"))
      (node (ref "JP3") (pin "1") (pinfunction "1_1") (pintype "passive"))
    )
    (net (code "67") (name "Net-(IC8A-PB5)") (class "Default")
      (node (ref "IC8") (pin "15") (pinfunction "PB5_15") (pintype "bidirectional"))
      (node (ref "JP3") (pin "3") (pinfunction "3_3") (pintype "passive"))
    )
    (net (code "68") (name "Net-(IC8A-PB6)") (class "Default")
      (node (ref "IC8") (pin "16") (pinfunction "PB6_16") (pintype "bidirectional"))
      (node (ref "JP3") (pin "5") (pinfunction "5_5") (pintype "passive"))
    )
    (net (code "69") (name "Net-(IC8A-PB7)") (class "Default")
      (node (ref "IC8") (pin "17") (pinfunction "PB7_17") (pintype "bidirectional"))
      (node (ref "JP3") (pin "7") (pinfunction "7_7") (pintype "passive"))
    )
    (net (code "70") (name "Net-(S1-S)") (class "Default")
      (node (ref "R5") (pin "1") (pinfunction "1_1") (pintype "passive"))
      (node (ref "S1") (pin "1") (pinfunction "S_1") (pintype "passive"))
      (node (ref "S1") (pin "2") (pinfunction "S1_2") (pintype "passive"))
    )
    (net (code "71") (name "Net-(U$1A-~{WE})") (class "Default")
      (node (ref "JP5") (pin "2") (pinfunction "2_2") (pintype "passive"))
      (node (ref "U$1") (pin "27") (pinfunction "~{WE}_27") (pintype "input"))
    )
    (net (code "72") (name "PU1") (class "Default")
      (node (ref "RN1") (pin "2") (pinfunction "2_2") (pintype "passive"))
    )
    (net (code "73") (name "PU2") (class "Default")
      (node (ref "IC6") (pin "1") (pinfunction "CLR_1") (pintype "input"))
      (node (ref "IC6") (pin "10") (pinfunction "PRE_10") (pintype "input"))
      (node (ref "IC6") (pin "13") (pinfunction "CLR_13") (pintype "input"))
      (node (ref "IC6") (pin "4") (pinfunction "PRE_4") (pintype "input"))
      (node (ref "IC7") (pin "11") (pinfunction "I_11") (pintype "input"))
      (node (ref "IC7") (pin "13") (pinfunction "I_13") (pintype "input"))
      (node (ref "IC7") (pin "5") (pinfunction "I_5") (pintype "input"))
      (node (ref "IC7") (pin "9") (pinfunction "I_9") (pintype "input"))
      (node (ref "RN1") (pin "3") (pinfunction "3_3") (pintype "passive"))
    )
    (net (code "74") (name "Q") (class "Default")
      (node (ref "IC1") (pin "35") (pinfunction "Q_35") (pintype "output"))
      (node (ref "IC6") (pin "5") (pinfunction "Q_5") (pintype "output"))
    )
    (net (code "75") (name "RESET") (class "Default")
      (node (ref "C1") (pin "+") (pinfunction "+_+") (pintype "passive"))
      (node (ref "D1") (pin "A") (pinfunction "A_A") (pintype "passive"))
      (node (ref "IC1") (pin "37") (pinfunction "RESET_37") (pintype "input"))
      (node (ref "IC8") (pin "34") (pinfunction "RESET_34") (pintype "input"))
      (node (ref "JP1") (pin "25") (pinfunction "25_25") (pintype "passive"))
      (node (ref "R5") (pin "2") (pinfunction "2_2") (pintype "passive"))
      (node (ref "RN1") (pin "5") (pinfunction "5_5") (pintype "passive"))
    )
    (net (code "76") (name "R{slash}W") (class "Default")
      (node (ref "IC1") (pin "32") (pinfunction "R/~{W}_32") (pintype "output"))
      (node (ref "IC2") (pin "4") (pinfunction "I0_4") (pintype "input"))
      (node (ref "IC2") (pin "5") (pinfunction "I1_5") (pintype "input"))
      (node (ref "IC2") (pin "9") (pinfunction "I0_9") (pintype "input"))
      (node (ref "IC5") (pin "13") (pinfunction "R/~{W}_13") (pintype "input"))
      (node (ref "IC8") (pin "21") (pinfunction "R/~{W}_21") (pintype "input"))
    )
    (net (code "77") (name "unconnected-(IC1A-BS-Pad5)") (class "Default")
      (node (ref "IC1") (pin "5") (pinfunction "BS_5") (pintype "output"))
    )
    (net (code "78") (name "unconnected-(IC5A-RTS-Pad5)") (class "Default")
      (node (ref "IC5") (pin "5") (pinfunction "RTS_5") (pintype "output"))
    )
    (net (code "79") (name "unconnected-(IC7C-O-Pad6)") (class "Default")
      (node (ref "IC7") (pin "6") (pinfunction "O_6") (pintype "output"))
    )
    (net (code "80") (name "unconnected-(IC7D-O-Pad8)") (class "Default")
      (node (ref "IC7") (pin "8") (pinfunction "O_8") (pintype "output"))
    )
    (net (code "81") (name "unconnected-(IC7E-O-Pad10)") (class "Default")
      (node (ref "IC7") (pin "10") (pinfunction "O_10") (pintype "output"))
    )
    (net (code "82") (name "unconnected-(IC7F-O-Pad12)") (class "Default")
      (node (ref "IC7") (pin "12") (pinfunction "O_12") (pintype "output"))
    )
    (net (code "83") (name "unconnected-(JP1-Pad30)") (class "Default")
      (node (ref "JP1") (pin "30") (pinfunction "30_30") (pintype "passive"))
    )
    (net (code "84") (name "{slash}BUSACK") (class "Default")
      (node (ref "IC1") (pin "6") (pinfunction "BA_6") (pintype "output"))
      (node (ref "JP1") (pin "28") (pinfunction "28_28") (pintype "passive"))
    )
    (net (code "85") (name "{slash}BUSRQ") (class "Default")
      (node (ref "IC1") (pin "40") (pinfunction "HALT_40") (pintype "input"))
      (node (ref "JP1") (pin "27") (pinfunction "27_27") (pintype "passive"))
      (node (ref "RN1") (pin "9") (pinfunction "9_9") (pintype "passive"))
    )
    (net (code "86") (name "{slash}FIRQ") (class "Default")
      (node (ref "IC1") (pin "4") (pinfunction "FIRQ_4") (pintype "input"))
      (node (ref "JP1") (pin "29") (pinfunction "29_29") (pintype "passive"))
      (node (ref "RN1") (pin "6") (pinfunction "6_6") (pintype "passive"))
    )
    (net (code "87") (name "{slash}IRQ") (class "Default")
      (node (ref "IC1") (pin "3") (pinfunction "IRQ_3") (pintype "input"))
      (node (ref "IC5") (pin "7") (pinfunction "IRQ_7") (pintype "output"))
      (node (ref "IC8") (pin "37") (pinfunction "IRQB_37") (pintype "open_collector"))
      (node (ref "IC8") (pin "38") (pinfunction "IRQA_38") (pintype "open_collector"))
      (node (ref "JP1") (pin "23") (pinfunction "23_23") (pintype "passive"))
      (node (ref "RN1") (pin "7") (pinfunction "7_7") (pintype "passive"))
    )
    (net (code "88") (name "{slash}NMI") (class "Default")
      (node (ref "IC1") (pin "2") (pinfunction "NMI_2") (pintype "input"))
      (node (ref "RN1") (pin "8") (pinfunction "8_8") (pintype "passive"))
    )
    (net (code "89") (name "{slash}RD") (class "Default")
      (node (ref "IC2") (pin "8") (pinfunction "O_8") (pintype "output"))
      (node (ref "IC3") (pin "22") (pinfunction "~{OE}_22") (pintype "input"))
      (node (ref "JP1") (pin "13") (pinfunction "13_13") (pintype "passive"))
      (node (ref "U$1") (pin "22") (pinfunction "~{OE}_22") (pintype "input"))
    )
    (net (code "90") (name "{slash}ROMCS") (class "Default")
      (node (ref "IC2") (pin "3") (pinfunction "O_3") (pintype "output"))
      (node (ref "U$1") (pin "20") (pinfunction "~{CE}_20") (pintype "input"))
    )
    (net (code "91") (name "{slash}WAIT") (class "Default")
      (node (ref "IC1") (pin "36") (pinfunction "MRDY_36") (pintype "input"))
      (node (ref "JP1") (pin "26") (pinfunction "26_26") (pintype "passive"))
      (node (ref "RN1") (pin "4") (pinfunction "4_4") (pintype "passive"))
    )
    (net (code "92") (name "{slash}WR") (class "Default")
      (node (ref "IC2") (pin "11") (pinfunction "O_11") (pintype "output"))
      (node (ref "IC3") (pin "27") (pinfunction "~{WE}_27") (pintype "input"))
      (node (ref "JP1") (pin "1") (pinfunction "1_1") (pintype "passive"))
      (node (ref "JP5") (pin "3") (pinfunction "3_3") (pintype "passive"))
    )
  )
)
